# Sch_Dr_SBUS.net
KiCad netlist of a schematic drawn in Altium Designer
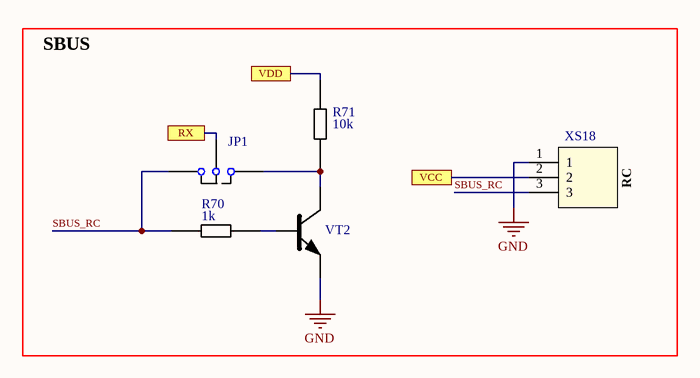
[diagram p0: Sch_Dr_SBUS .SchDoc]

(export (version "E")
  (design (tool "Eeschema 10.0.6"))
  (components
    (comp (ref "JP1") (value "Jumper") (footprint "Jumper") (libsource (lib "Dr_lib") (part "Jumper")))
    (comp (ref "R70")
      (value "1k")
      (footprint "Res_0603")
      (description "CR-03FL7----1K")
      (libsource (lib "") (part "Res__1"))
    )
    (comp (ref "R71")
      (value "10k")
      (footprint "Res_0603")
      (description "CR-03FL7---10K")
      (libsource (lib "Dr_lib") (part "Res_"))
    )
    (comp (ref "VT2")
      (value "MMBT3904")
      (footprint "SOT-23-3")
      (description "SOT-23, -40V, -0.2A, PNP Bipolar Transistor")
      (libsource (lib "Dr_lib") (part "MMBT3904"))
    )
    (comp (ref "XS18") (value "PLS-3") (footprint "3X") (libsource (lib "Dr_lib") (part "PLS-3")))
  )
  (nets
    (net (code "1") (name "/RX") (class "Default")
      (node (ref "JP1") (pin "2") (pinfunction "2_2") (pintype "passive"))
    )
    (net (code "2") (name "/SBUS_RC") (class "Default")
      (node (ref "JP1") (pin "3") (pinfunction "3_3") (pintype "passive"))
      (node (ref "R70") (pin "1") (pinfunction "1_1") (pintype "passive"))
      (node (ref "XS18") (pin "3") (pinfunction "3_3") (pintype "passive"))
    )
    (net (code "3") (name "/VCC") (class "Default")
      (node (ref "XS18") (pin "2") (pinfunction "2_2") (pintype "passive"))
    )
    (net (code "4") (name "/VDD") (class "Default")
      (node (ref "R71") (pin "1") (pinfunction "1_1") (pintype "passive"))
    )
    (net (code "5") (name "GND") (class "Default")
      (node (ref "VT2") (pin "2") (pinfunction "E_2") (pintype "passive"))
      (node (ref "XS18") (pin "1") (pinfunction "1_1") (pintype "passive"))
    )
    (net (code "6") (name "Net-(VT2-B)") (class "Default")
      (node (ref "R70") (pin "2") (pinfunction "2_2") (pintype "passive"))
      (node (ref "VT2") (pin "1") (pinfunction "B_1") (pintype "passive"))
    )
    (net (code "7") (name "Net-(VT2-C)") (class "Default")
      (node (ref "JP1") (pin "1") (pinfunction "1_1") (pintype "passive"))
      (node (ref "R71") (pin "2") (pinfunction "2_2") (pintype "passive"))
      (node (ref "VT2") (pin "3") (pinfunction "C_3") (pintype "passive"))
    )
  )
)
